# USB_Snoop.net
KiCad netlist of a schematic drawn in EAGLE
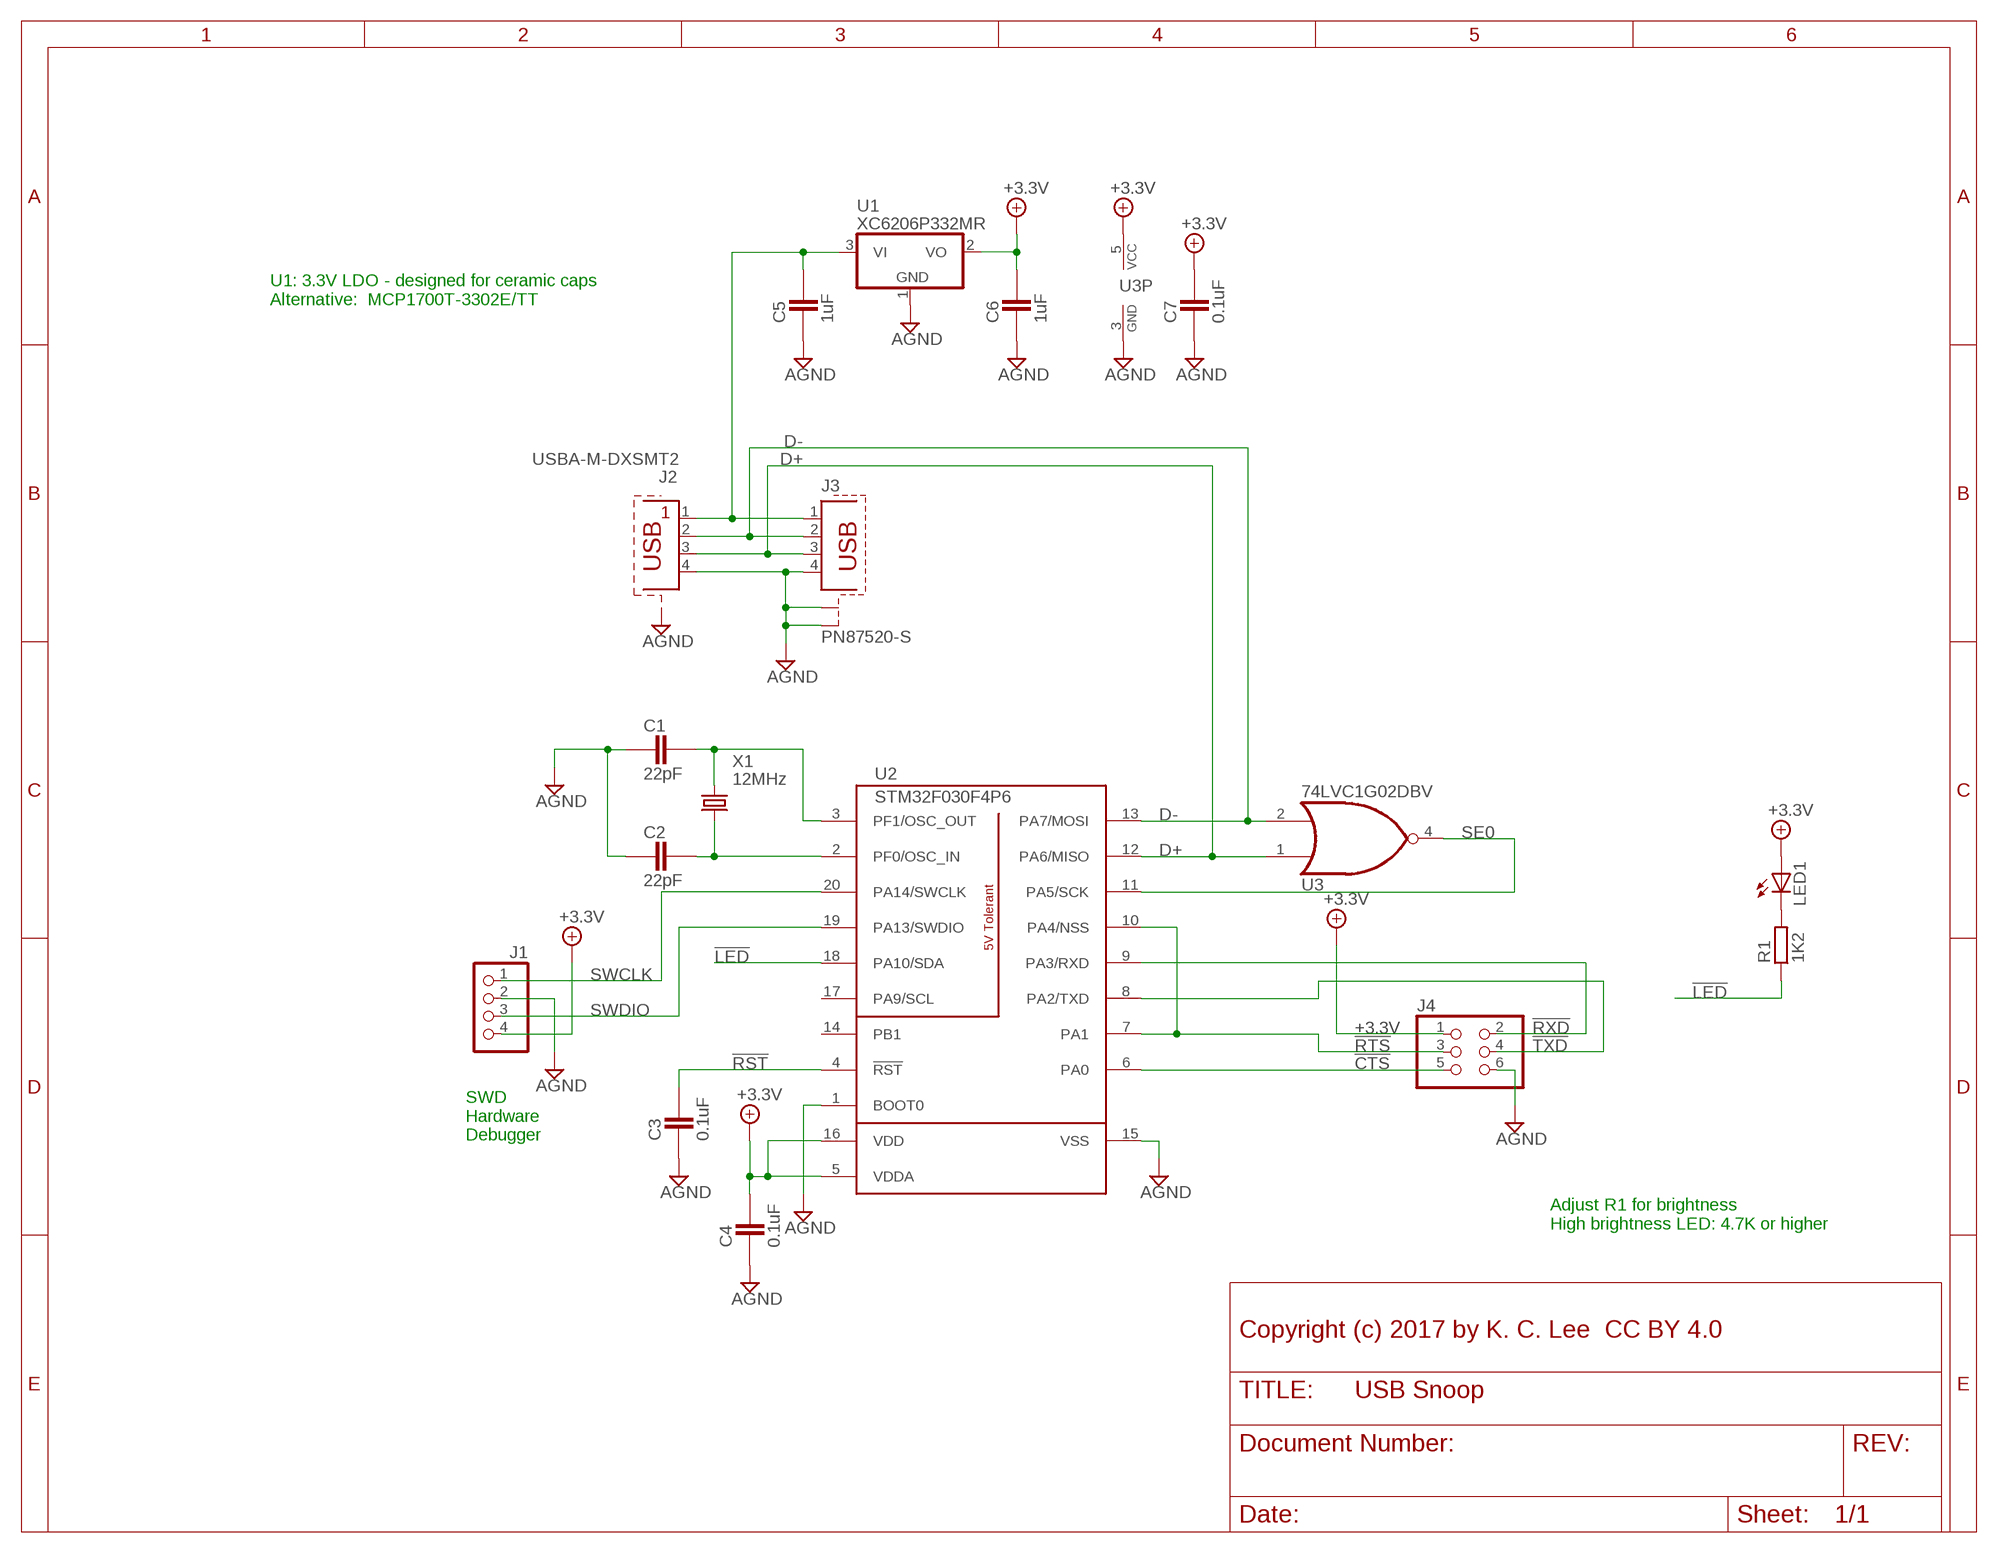
[diagram p0: schematic, sheet 1]

(export (version "E")
  (design (tool "Eeschema 10.0.6"))
  (components
    (comp (ref "C1")
      (value "22pF")
      (footprint "eagle-import:CAPC1608X92N")
      (libsource (lib "eagle-import") (part "CAPACITOR_0603"))
    )
    (comp (ref "C2")
      (value "22pF")
      (footprint "eagle-import:CAPC1608X92N")
      (libsource (lib "eagle-import") (part "CAPACITOR_0603"))
    )
    (comp (ref "C3")
      (value "0.1uF")
      (footprint "eagle-import:CAPC1608X92N")
      (libsource (lib "eagle-import") (part "CAPACITOR_0603"))
    )
    (comp (ref "C4")
      (value "0.1uF")
      (footprint "eagle-import:CAPC1608X92N")
      (libsource (lib "eagle-import") (part "CAPACITOR_0603"))
    )
    (comp (ref "C5")
      (value "1uF")
      (footprint "eagle-import:CAPC1608X92N")
      (fields (field (name "PARTNO") "STOCK: 1UF/10V 20% TDK"))
      (libsource (lib "eagle-import") (part "CAPACITOR_0603"))
    )
    (comp (ref "C6")
      (value "1uF")
      (footprint "eagle-import:CAPC1608X92N")
      (fields (field (name "PARTNO") "STOCK: 1UF/10V 20% TDK"))
      (libsource (lib "eagle-import") (part "CAPACITOR_0603"))
    )
    (comp (ref "C7")
      (value "0.1uF")
      (footprint "eagle-import:CAPC1608X92N")
      (libsource (lib "eagle-import") (part "CAPACITOR_0603"))
    )
    (comp (ref "J1")
      (value "PINHD-1X4_2.54")
      (footprint "eagle-import:1X04")
      (fields (field (name "PARTNO") "1X04 HEADER 2.54MM"))
      (libsource (lib "eagle-import") (part "PINHD-1X4_2.54"))
    )
    (comp (ref "J2")
      (value "USBA-M-DXSMT2")
      (footprint "eagle-import:CHINESE_USB_M_SMT-2")
      (libsource (lib "eagle-import") (part "USBA-M-DXSMT2"))
    )
    (comp (ref "J3")
      (value "PN87520-S")
      (footprint "eagle-import:PN87520-S")
      (libsource (lib "eagle-import") (part "PN87520-S"))
    )
    (comp (ref "J4")
      (value "PINHD-2X3_2.00")
      (footprint "eagle-import:2X03M_TH")
      (libsource (lib "eagle-import") (part "PINHD-2X3_2.00"))
    )
    (comp (ref "LED1")
      (value "LEDSML0603")
      (footprint "eagle-import:SML0603")
      (libsource (lib "eagle-import") (part "LEDSML0603"))
    )
    (comp (ref "R1")
      (value "1K2")
      (footprint "eagle-import:RESC1608X55N")
      (libsource (lib "eagle-import") (part "RESISTOR_0603"))
    )
    (comp (ref "U1")
      (value "XC6206P332MR")
      (footprint "eagle-import:SOT95P280X135-3N")
      (libsource (lib "eagle-import") (part "MCP1700/TT"))
    )
    (comp (ref "U2")
      (value "STM32F030F4P6")
      (footprint "eagle-import:TSSOP20")
      (libsource (lib "eagle-import") (part "STM32F030F4P6"))
    )
    (comp (ref "U3")
      (value "74LVC1G02DBV")
      (footprint "eagle-import:SOT23-5")
      (fields (field (name "PARTNO") "*"))
      (libsource (lib "eagle-import") (part "741G02DBVLVC"))
    )
    (comp (ref "X1")
      (value "12MHz")
      (footprint "eagle-import:TC26H")
      (libsource (lib "eagle-import") (part "CRYSTALTC26H"))
    )
  )
  (nets
    (net (code "1") (name "+3.3V") (class "Default")
      (node (ref "C4") (pin "2") (pinfunction "2_2") (pintype "passive"))
      (node (ref "C6") (pin "2") (pinfunction "2_2") (pintype "passive"))
      (node (ref "C7") (pin "2") (pinfunction "2_2") (pintype "passive"))
      (node (ref "J1") (pin "4") (pinfunction "4_4") (pintype "passive"))
      (node (ref "J4") (pin "1") (pinfunction "1_1") (pintype "passive"))
      (node (ref "LED1") (pin "A") (pinfunction "A_A") (pintype "passive"))
      (node (ref "U1") (pin "2") (pinfunction "VO_2") (pintype "passive"))
      (node (ref "U2") (pin "16") (pinfunction "VDD_16") (pintype "input"))
      (node (ref "U2") (pin "5") (pinfunction "VDDA_5") (pintype "input"))
      (node (ref "U3") (pin "5") (pinfunction "VCC_5") (pintype "power_in"))
    )
    (net (code "2") (name "/D+") (class "Default")
      (node (ref "J2") (pin "3") (pinfunction "3_3") (pintype "passive"))
      (node (ref "J3") (pin "3") (pinfunction "3_3") (pintype "passive"))
      (node (ref "U2") (pin "12") (pinfunction "PA6/MISO_12") (pintype "bidirectional"))
      (node (ref "U3") (pin "1") (pinfunction "I0_1") (pintype "input"))
    )
    (net (code "3") (name "/D-") (class "Default")
      (node (ref "J2") (pin "2") (pinfunction "2_2") (pintype "passive"))
      (node (ref "J3") (pin "2") (pinfunction "2_2") (pintype "passive"))
      (node (ref "U2") (pin "13") (pinfunction "PA7/MOSI_13") (pintype "bidirectional"))
      (node (ref "U3") (pin "2") (pinfunction "I1_2") (pintype "input"))
    )
    (net (code "4") (name "/SE0") (class "Default")
      (node (ref "U2") (pin "11") (pinfunction "PA5/SCK_11") (pintype "bidirectional"))
      (node (ref "U3") (pin "4") (pinfunction "O_4") (pintype "output"))
    )
    (net (code "5") (name "/SWCLK") (class "Default")
      (node (ref "J1") (pin "1") (pinfunction "1_1") (pintype "passive"))
      (node (ref "U2") (pin "20") (pinfunction "PA14/SWCLK_20") (pintype "bidirectional"))
    )
    (net (code "6") (name "/SWDIO") (class "Default")
      (node (ref "J1") (pin "3") (pinfunction "3_3") (pintype "passive"))
      (node (ref "U2") (pin "19") (pinfunction "PA13/SWDIO_19") (pintype "bidirectional"))
    )
    (net (code "7") (name "/~{CTS}") (class "Default")
      (node (ref "J4") (pin "5") (pinfunction "5_5") (pintype "passive"))
      (node (ref "U2") (pin "6") (pinfunction "PA0_6") (pintype "bidirectional"))
    )
    (net (code "8") (name "/~{LED}") (class "Default")
      (node (ref "R1") (pin "1") (pinfunction "1_1") (pintype "passive"))
      (node (ref "U2") (pin "18") (pinfunction "PA10/SDA_18") (pintype "bidirectional"))
    )
    (net (code "9") (name "/~{RST}") (class "Default")
      (node (ref "C3") (pin "2") (pinfunction "2_2") (pintype "passive"))
      (node (ref "U2") (pin "4") (pinfunction "~{RST}_4") (pintype "input"))
    )
    (net (code "10") (name "/~{RTS}") (class "Default")
      (node (ref "J4") (pin "3") (pinfunction "3_3") (pintype "passive"))
      (node (ref "U2") (pin "10") (pinfunction "PA4/NSS_10") (pintype "bidirectional"))
      (node (ref "U2") (pin "7") (pinfunction "PA1_7") (pintype "bidirectional"))
    )
    (net (code "11") (name "/~{RXD}") (class "Default")
      (node (ref "J4") (pin "2") (pinfunction "2_2") (pintype "passive"))
      (node (ref "U2") (pin "9") (pinfunction "PA3/RXD_9") (pintype "bidirectional"))
    )
    (net (code "12") (name "/~{TXD}") (class "Default")
      (node (ref "J4") (pin "4") (pinfunction "4_4") (pintype "passive"))
      (node (ref "U2") (pin "8") (pinfunction "PA2/TXD_8") (pintype "bidirectional"))
    )
    (net (code "13") (name "AGND") (class "Default")
      (node (ref "C1") (pin "1") (pinfunction "1_1") (pintype "passive"))
      (node (ref "C2") (pin "1") (pinfunction "1_1") (pintype "passive"))
      (node (ref "C3") (pin "1") (pinfunction "1_1") (pintype "passive"))
      (node (ref "C4") (pin "1") (pinfunction "1_1") (pintype "passive"))
      (node (ref "C5") (pin "1") (pinfunction "1_1") (pintype "passive"))
      (node (ref "C6") (pin "1") (pinfunction "1_1") (pintype "passive"))
      (node (ref "C7") (pin "1") (pinfunction "1_1") (pintype "passive"))
      (node (ref "J1") (pin "2") (pinfunction "2_2") (pintype "passive"))
      (node (ref "J2") (pin "4") (pinfunction "4_4") (pintype "passive"))
      (node (ref "J2") (pin "S1") (pinfunction "S1_S1") (pintype "passive"))
      (node (ref "J2") (pin "S2") (pinfunction "S1_S2") (pintype "passive"))
      (node (ref "J3") (pin "4") (pinfunction "4_4") (pintype "passive"))
      (node (ref "J3") (pin "S1") (pinfunction "S1_S1") (pintype "passive"))
      (node (ref "J3") (pin "S2") (pinfunction "S2_S2") (pintype "passive"))
      (node (ref "J4") (pin "6") (pinfunction "6_6") (pintype "passive"))
      (node (ref "U1") (pin "1") (pinfunction "GND_1") (pintype "passive"))
      (node (ref "U2") (pin "1") (pinfunction "BOOT0_1") (pintype "input"))
      (node (ref "U2") (pin "15") (pinfunction "VSS_15") (pintype "input"))
      (node (ref "U3") (pin "3") (pinfunction "GND_3") (pintype "power_in"))
    )
    (net (code "14") (name "Net-(LED1-PadC)") (class "Default")
      (node (ref "LED1") (pin "C") (pinfunction "C_C") (pintype "passive"))
      (node (ref "R1") (pin "2") (pinfunction "2_2") (pintype "passive"))
    )
    (net (code "15") (name "Net-(U1-VI)") (class "Default")
      (node (ref "C5") (pin "2") (pinfunction "2_2") (pintype "passive"))
      (node (ref "J2") (pin "1") (pinfunction "1_1") (pintype "passive"))
      (node (ref "J3") (pin "1") (pinfunction "1_1") (pintype "passive"))
      (node (ref "U1") (pin "3") (pinfunction "VI_3") (pintype "input"))
    )
    (net (code "16") (name "Net-(U2-PF0{slash}OSC_IN)") (class "Default")
      (node (ref "C2") (pin "2") (pinfunction "2_2") (pintype "passive"))
      (node (ref "U2") (pin "2") (pinfunction "PF0/OSC_IN_2") (pintype "input"))
      (node (ref "X1") (pin "2") (pinfunction "2_2") (pintype "passive"))
    )
    (net (code "17") (name "Net-(U2-PF1{slash}OSC_OUT)") (class "Default")
      (node (ref "C1") (pin "2") (pinfunction "2_2") (pintype "passive"))
      (node (ref "U2") (pin "3") (pinfunction "PF1/OSC_OUT_3") (pintype "output"))
      (node (ref "X1") (pin "1") (pinfunction "1_1") (pintype "passive"))
    )
    (net (code "18") (name "unconnected-(U2-PA9{slash}SCL-Pad17)") (class "Default")
      (node (ref "U2") (pin "17") (pinfunction "PA9/SCL_17") (pintype "bidirectional"))
    )
    (net (code "19") (name "unconnected-(U2-PB1-Pad14)") (class "Default")
      (node (ref "U2") (pin "14") (pinfunction "PB1_14") (pintype "bidirectional"))
    )
  )
)
